# AK4430_2.net
KiCad netlist of a schematic drawn in Altium Designer
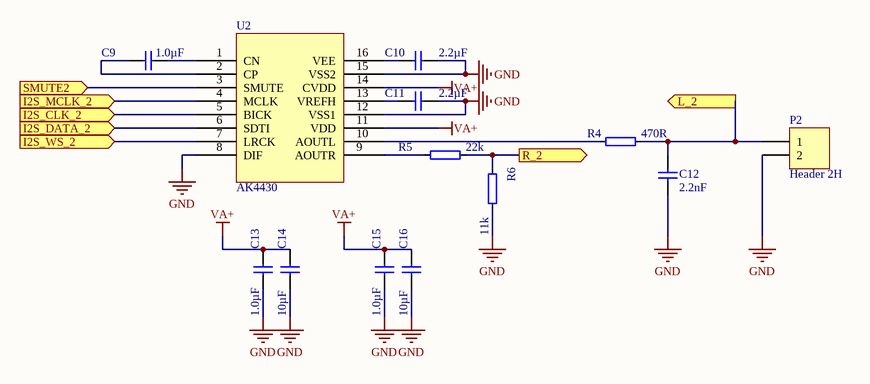
[diagram p0: AK4430_2.SchDoc]

(export (version "E")
  (design (tool "Eeschema 10.0.6"))
  (components
    (comp (ref "C9")
      (value "1.0µF")
      (footprint "0603s")
      (description "Chip Cap 0603")
      (fields (field (name "PART NUMBER") "C0603-1µ0") (field (name "PUBLISHER") "Nordic Semiconductor"))
      (libsource (lib "Nordic Passive DB") (part "CAP"))
    )
    (comp (ref "C10")
      (value "2.2µF")
      (footprint "0603s")
      (description "Chip Cap 0603")
      (fields (field (name "PART NUMBER") "C0603-2µ2") (field (name "PUBLISHER") "Nordic Semiconductor"))
      (libsource (lib "Nordic Passive DB") (part "CAP"))
    )
    (comp (ref "C11")
      (value "2.2µF")
      (footprint "0603s")
      (description "Chip Cap 0603")
      (fields (field (name "PART NUMBER") "C0603-2µ2") (field (name "PUBLISHER") "Nordic Semiconductor"))
      (libsource (lib "Nordic Passive DB") (part "CAP"))
    )
    (comp (ref "C12")
      (value "2.2nF")
      (footprint "0402s")
      (description "Chip Cap 0402")
      (fields (field (name "PART NUMBER") "C0402-2n2") (field (name "PUBLISHER") "Nordic Semiconductor"))
      (libsource (lib "Nordic Passive DB") (part "CAP"))
    )
    (comp (ref "C13")
      (value "1.0µF")
      (footprint "0603s")
      (description "Chip Cap 0603")
      (fields (field (name "PART NUMBER") "C0603-1µ0") (field (name "PUBLISHER") "Nordic Semiconductor"))
      (libsource (lib "Nordic Passive DB") (part "CAP"))
    )
    (comp (ref "C14")
      (value "10µF")
      (footprint "0805")
      (description "Chip Cap 0805")
      (fields (field (name "PART NUMBER") "C0805-10µ") (field (name "PUBLISHER") "Nordic Semiconductor"))
      (libsource (lib "Nordic Passive DB") (part "CAP"))
    )
    (comp (ref "C15")
      (value "1.0µF")
      (footprint "0603s")
      (description "Chip Cap 0603")
      (fields (field (name "PART NUMBER") "C0603-1µ0") (field (name "PUBLISHER") "Nordic Semiconductor"))
      (libsource (lib "Nordic Passive DB") (part "CAP"))
    )
    (comp (ref "C16")
      (value "10µF")
      (footprint "0805")
      (description "Chip Cap 0805")
      (fields (field (name "PART NUMBER") "C0805-10µ") (field (name "PUBLISHER") "Nordic Semiconductor"))
      (libsource (lib "Nordic Passive DB") (part "CAP"))
    )
    (comp (ref "P2")
      (value "Header 2H")
      (footprint "RCA")
      (description "Header, 2-Pin, Right Angle")
      (fields (field (name "PUBLISHER") "Altium Limited"))
      (libsource (lib "Miscellaneous Connectors") (part "Header 2H"))
    )
    (comp (ref "R4")
      (value "470R")
      (footprint "0402s")
      (description "Chip Res 0402")
      (fields (field (name "PART NUMBER") "R0402-470") (field (name "PUBLISHER") "Nordic Semiconductor"))
      (libsource (lib "Nordic Passive DB") (part "RES_1"))
    )
    (comp (ref "R5")
      (value "22k")
      (footprint "0402s")
      (description "Chip Res 0402")
      (fields (field (name "PART NUMBER") "R0402-22k") (field (name "PUBLISHER") "Nordic Semiconductor"))
      (libsource (lib "Nordic Passive DB") (part "RES_1"))
    )
    (comp (ref "R6")
      (value "11k")
      (footprint "0402s")
      (description "Chip Res 0402")
      (fields (field (name "PART NUMBER") "R0402-10k") (field (name "PUBLISHER") "Nordic Semiconductor"))
      (libsource (lib "Nordic Passive DB") (part "RES_1"))
    )
    (comp (ref "U2")
      (value "AK4430")
      (footprint "TSOP65P640X110-16N")
      (libsource (lib "nRF2460") (part "AK4430"))
    )
  )
  (nets
    (net (code "1") (name "/I2S_CLK_2") (class "Default")
      (node (ref "U2") (pin "5") (pinfunction "BICK_5") (pintype "passive"))
    )
    (net (code "2") (name "/I2S_DATA_2") (class "Default")
      (node (ref "U2") (pin "6") (pinfunction "SDTI_6") (pintype "passive"))
    )
    (net (code "3") (name "/I2S_MCLK_2") (class "Default")
      (node (ref "U2") (pin "4") (pinfunction "MCLK_4") (pintype "passive"))
    )
    (net (code "4") (name "/I2S_WS_2") (class "Default")
      (node (ref "U2") (pin "7") (pinfunction "LRCK_7") (pintype "passive"))
    )
    (net (code "5") (name "/L_2") (class "Default")
      (node (ref "C12") (pin "2") (pinfunction "2_2") (pintype "passive"))
      (node (ref "P2") (pin "1") (pinfunction "1_1") (pintype "passive"))
      (node (ref "R4") (pin "2") (pinfunction "2_2") (pintype "passive"))
    )
    (net (code "6") (name "/R_2") (class "Default")
      (node (ref "R5") (pin "2") (pinfunction "2_2") (pintype "passive"))
      (node (ref "R6") (pin "2") (pinfunction "2_2") (pintype "passive"))
    )
    (net (code "7") (name "/SMUTE2") (class "Default")
      (node (ref "U2") (pin "3") (pinfunction "SMUTE_3") (pintype "passive"))
    )
    (net (code "8") (name "GND") (class "Default")
      (node (ref "C10") (pin "2") (pinfunction "2_2") (pintype "passive"))
      (node (ref "C11") (pin "2") (pinfunction "2_2") (pintype "passive"))
      (node (ref "C12") (pin "1") (pinfunction "1_1") (pintype "passive"))
      (node (ref "C13") (pin "1") (pinfunction "1_1") (pintype "passive"))
      (node (ref "C14") (pin "1") (pinfunction "1_1") (pintype "passive"))
      (node (ref "C15") (pin "1") (pinfunction "1_1") (pintype "passive"))
      (node (ref "C16") (pin "1") (pinfunction "1_1") (pintype "passive"))
      (node (ref "P2") (pin "2") (pinfunction "2_2") (pintype "passive"))
      (node (ref "R6") (pin "1") (pinfunction "1_1") (pintype "passive"))
      (node (ref "U2") (pin "12") (pinfunction "VSS1_12") (pintype "passive"))
      (node (ref "U2") (pin "15") (pinfunction "VSS2_15") (pintype "passive"))
      (node (ref "U2") (pin "8") (pinfunction "DIF_8") (pintype "passive"))
    )
    (net (code "9") (name "Net-(U2-AOUTL)") (class "Default")
      (node (ref "R4") (pin "1") (pinfunction "1_1") (pintype "passive"))
      (node (ref "U2") (pin "10") (pinfunction "AOUTL_10") (pintype "passive"))
    )
    (net (code "10") (name "Net-(U2-AOUTR)") (class "Default")
      (node (ref "R5") (pin "1") (pinfunction "1_1") (pintype "passive"))
      (node (ref "U2") (pin "9") (pinfunction "AOUTR_9") (pintype "passive"))
    )
    (net (code "11") (name "Net-(U2-CN)") (class "Default")
      (node (ref "C9") (pin "2") (pinfunction "2_2") (pintype "passive"))
      (node (ref "U2") (pin "1") (pinfunction "CN_1") (pintype "passive"))
    )
    (net (code "12") (name "Net-(U2-CP)") (class "Default")
      (node (ref "C9") (pin "1") (pinfunction "1_1") (pintype "passive"))
      (node (ref "U2") (pin "2") (pinfunction "CP_2") (pintype "passive"))
    )
    (net (code "13") (name "Net-(U2-VEE)") (class "Default")
      (node (ref "C10") (pin "1") (pinfunction "1_1") (pintype "passive"))
      (node (ref "U2") (pin "16") (pinfunction "VEE_16") (pintype "passive"))
    )
    (net (code "14") (name "Net-(U2-VREFH)") (class "Default")
      (node (ref "C11") (pin "1") (pinfunction "1_1") (pintype "passive"))
      (node (ref "U2") (pin "13") (pinfunction "VREFH_13") (pintype "passive"))
    )
    (net (code "15") (name "VA+") (class "Default")
      (node (ref "C13") (pin "2") (pinfunction "2_2") (pintype "passive"))
      (node (ref "C14") (pin "2") (pinfunction "2_2") (pintype "passive"))
      (node (ref "C15") (pin "2") (pinfunction "2_2") (pintype "passive"))
      (node (ref "C16") (pin "2") (pinfunction "2_2") (pintype "passive"))
      (node (ref "U2") (pin "11") (pinfunction "VDD_11") (pintype "passive"))
      (node (ref "U2") (pin "14") (pinfunction "CVDD_14") (pintype "passive"))
    )
  )
)
